# main_control.net
KiCad netlist of a schematic drawn in EasyEDA Pro
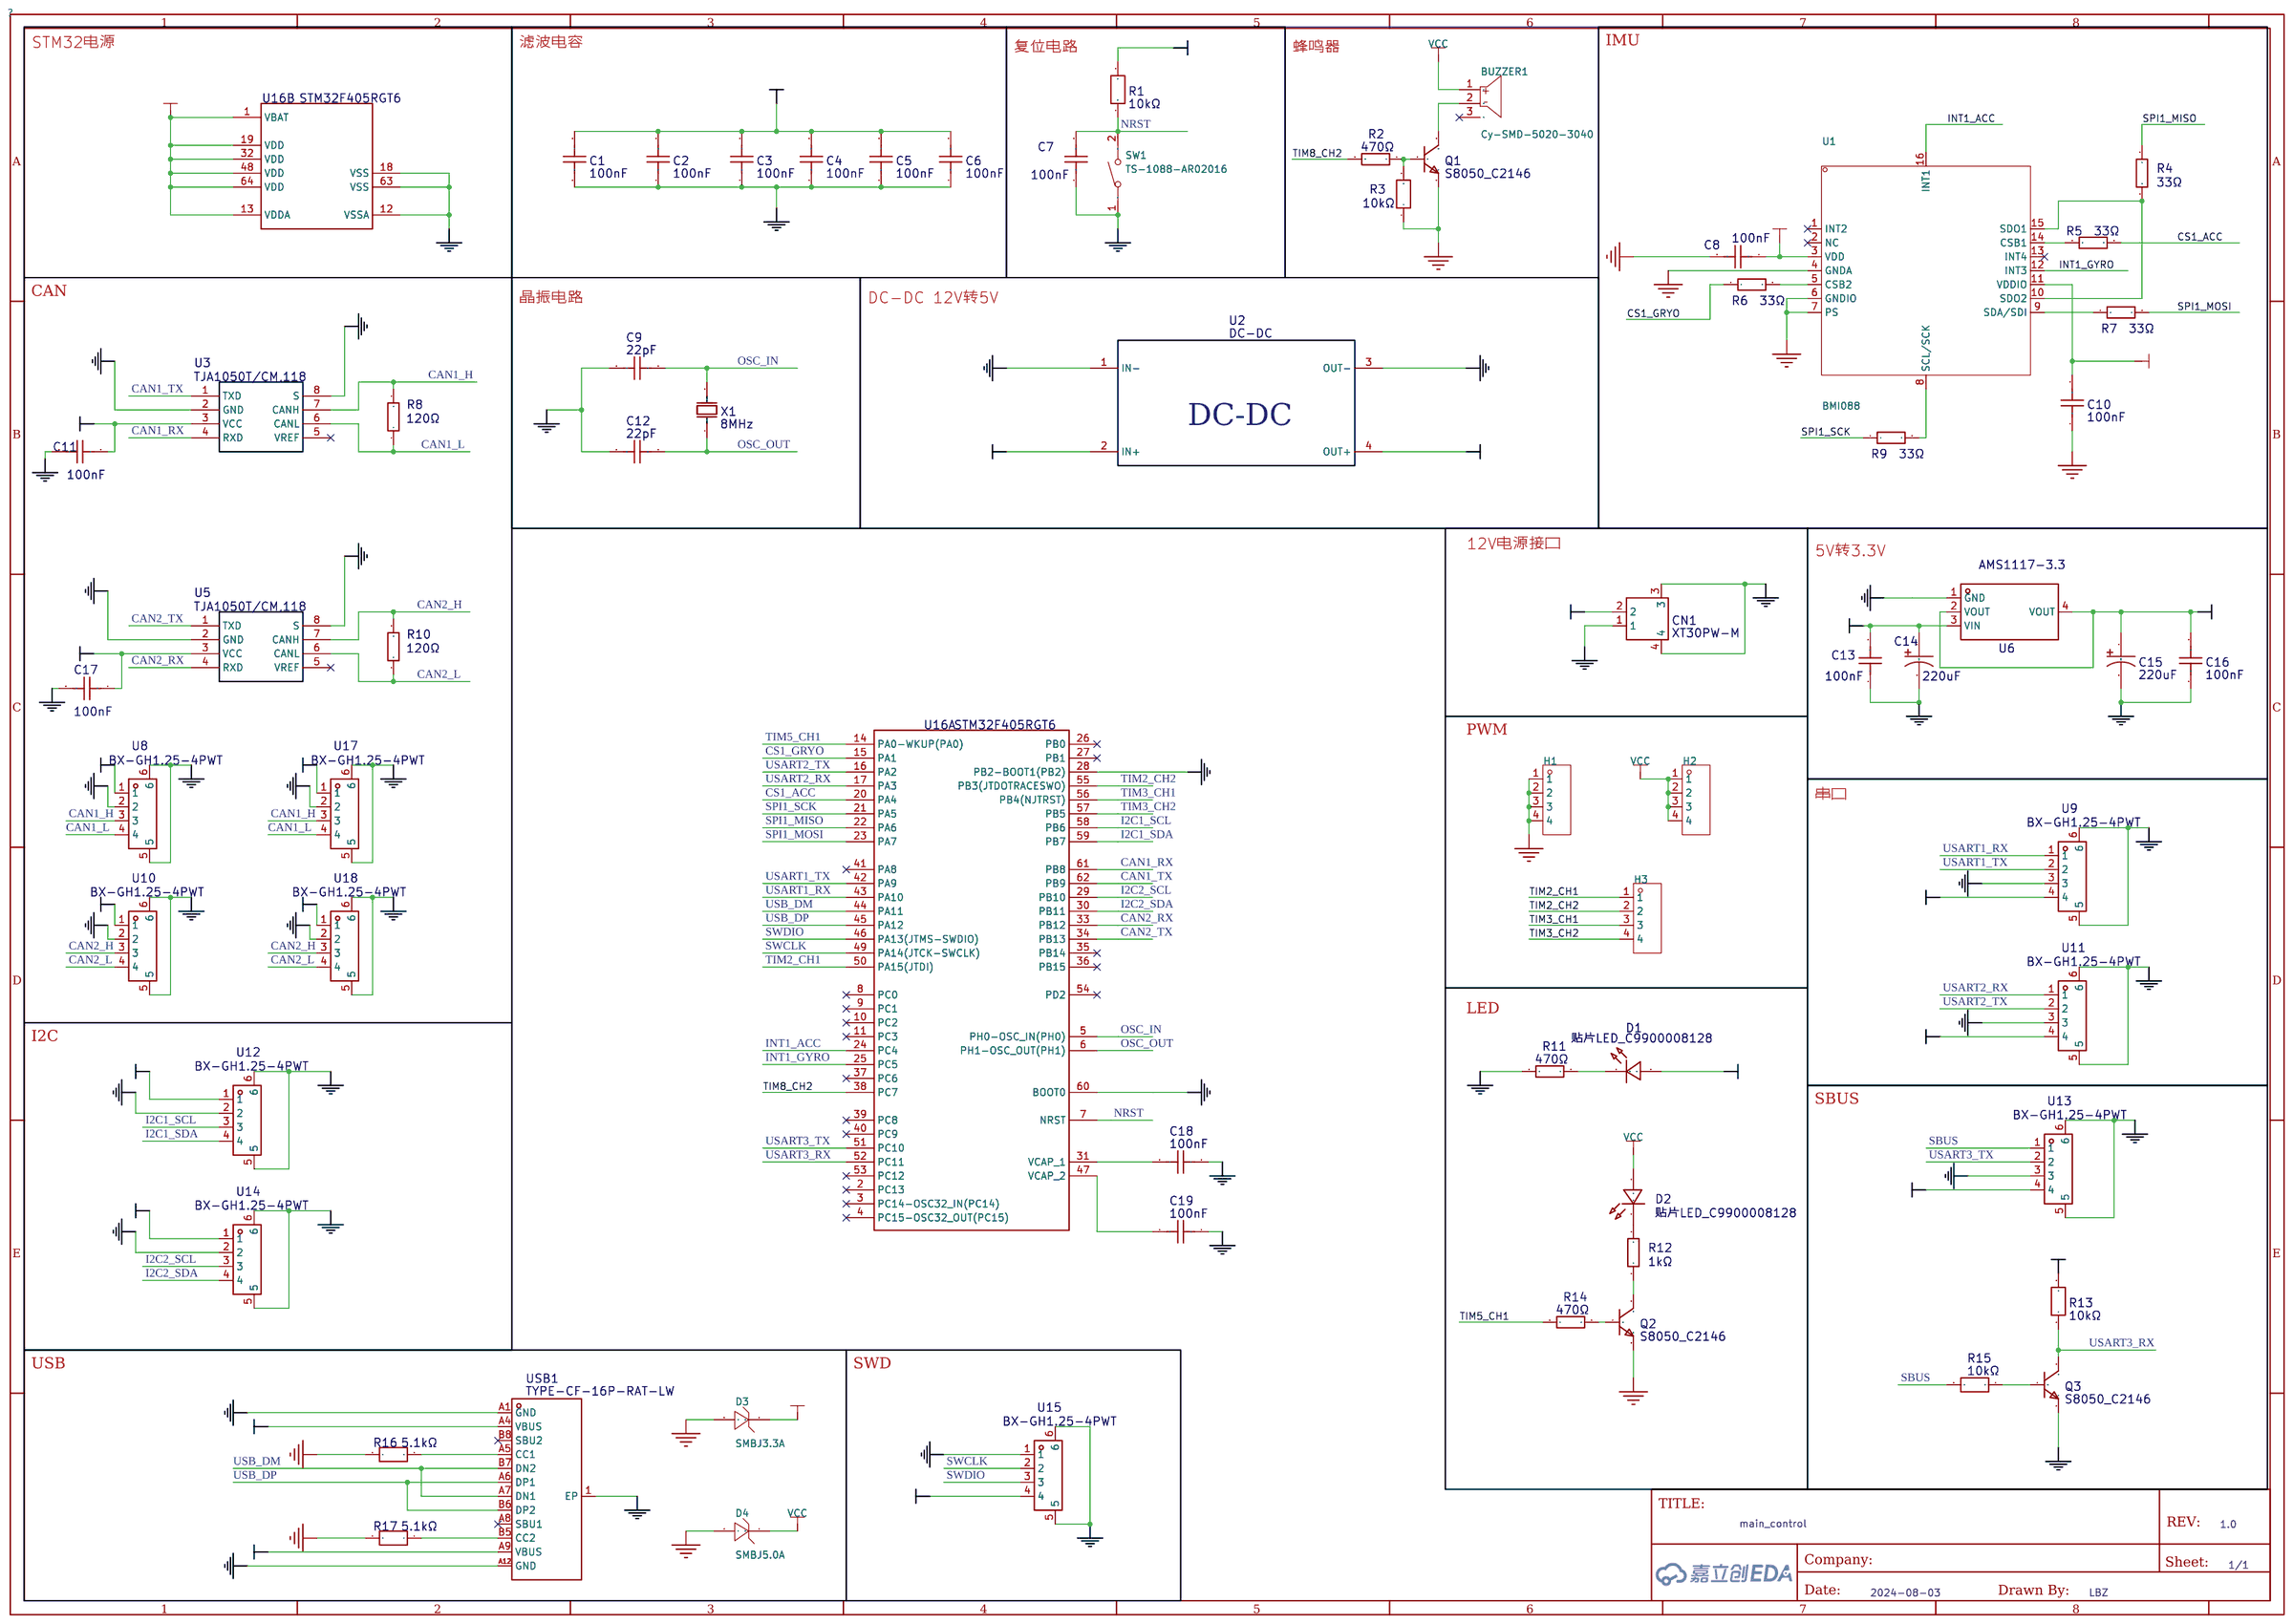
[diagram p0: schematic sheet]

(export (version "E")
  (design (tool "Eeschema 10.0.6"))
  (components
    (comp (ref "BUZZER1")
      (value "Cy-SMD-5020-3040")
      (footprint "easyedapro:BUZ-SMD_CY-SMD-5020-3040")
      (fields (field (name "Manufacturer") "CY(超音)"))
      (libsource (lib "easyedapro") (part "CY-SMD-5020-3040"))
    )
    (comp (ref "C1")
      (value "100nF")
      (footprint "easyedapro:C0603")
      (fields
        (field (name "Manufacturer Part") "0603J0250104KXR")
        (field (name "Manufacturer") "Knowles(楼氏)")
      )
      (libsource (lib "easyedapro") (part "100nF"))
    )
    (comp (ref "C2")
      (value "100nF")
      (footprint "easyedapro:C0603")
      (fields
        (field (name "Manufacturer Part") "0603J0250104KXR")
        (field (name "Manufacturer") "Knowles(楼氏)")
      )
      (libsource (lib "easyedapro") (part "100nF"))
    )
    (comp (ref "C3")
      (value "100nF")
      (footprint "easyedapro:C0603")
      (fields
        (field (name "Manufacturer Part") "0603J0250104KXR")
        (field (name "Manufacturer") "Knowles(楼氏)")
      )
      (libsource (lib "easyedapro") (part "100nF"))
    )
    (comp (ref "C4")
      (value "100nF")
      (footprint "easyedapro:C0603")
      (fields
        (field (name "Manufacturer Part") "0603J0250104KXR")
        (field (name "Manufacturer") "Knowles(楼氏)")
      )
      (libsource (lib "easyedapro") (part "100nF"))
    )
    (comp (ref "C5")
      (value "100nF")
      (footprint "easyedapro:C0603")
      (fields
        (field (name "Manufacturer Part") "0603J0250104KXR")
        (field (name "Manufacturer") "Knowles(楼氏)")
      )
      (libsource (lib "easyedapro") (part "100nF"))
    )
    (comp (ref "C6")
      (value "100nF")
      (footprint "easyedapro:C0603")
      (fields
        (field (name "Manufacturer Part") "0603J0250104KXR")
        (field (name "Manufacturer") "Knowles(楼氏)")
      )
      (libsource (lib "easyedapro") (part "100nF"))
    )
    (comp (ref "C7")
      (value "100nF")
      (footprint "easyedapro:C0603")
      (fields
        (field (name "Manufacturer Part") "0603J0250104KXR")
        (field (name "Manufacturer") "Knowles(楼氏)")
      )
      (libsource (lib "easyedapro") (part "100nF"))
    )
    (comp (ref "C8")
      (value "100nF")
      (footprint "easyedapro:C0603")
      (fields
        (field (name "Manufacturer Part") "0603J0250104KXR")
        (field (name "Manufacturer") "Knowles(楼氏)")
      )
      (libsource (lib "easyedapro") (part "100nF"))
    )
    (comp (ref "C9")
      (value "22pF")
      (footprint "easyedapro:C0603")
      (fields
        (field (name "Manufacturer Part") "0603J0250104KXR")
        (field (name "Manufacturer") "Knowles(楼氏)")
      )
      (libsource (lib "easyedapro") (part "22pF"))
    )
    (comp (ref "C10")
      (value "100nF")
      (footprint "easyedapro:C0603")
      (fields
        (field (name "Manufacturer Part") "0603J0250104KXR")
        (field (name "Manufacturer") "Knowles(楼氏)")
      )
      (libsource (lib "easyedapro") (part "100nF"))
    )
    (comp (ref "C11")
      (value "100nF")
      (footprint "easyedapro:C0603")
      (fields
        (field (name "Manufacturer Part") "0603J0250104KXR")
        (field (name "Manufacturer") "Knowles(楼氏)")
      )
      (libsource (lib "easyedapro") (part "100nF"))
    )
    (comp (ref "C12")
      (value "22pF")
      (footprint "easyedapro:C0603")
      (fields
        (field (name "Manufacturer Part") "0603J0250104KXR")
        (field (name "Manufacturer") "Knowles(楼氏)")
      )
      (libsource (lib "easyedapro") (part "22pF"))
    )
    (comp (ref "C13")
      (value "100nF")
      (footprint "easyedapro:C0603")
      (fields
        (field (name "Manufacturer Part") "0603J0250104KXR")
        (field (name "Manufacturer") "Knowles(楼氏)")
      )
      (libsource (lib "easyedapro") (part "100nF"))
    )
    (comp (ref "C14")
      (value "220uF")
      (footprint "easyedapro:CAP-SMD_BD6.3-L6.6-W6.6-FD")
      (fields
        (field (name "Manufacturer Part") "MVK 16V220M 6.3*8 6.3TP")
        (field (name "Manufacturer") "SAMYOUNG(韩国三莹)")
      )
      (libsource (lib "easyedapro") (part "220uF"))
    )
    (comp (ref "C15")
      (value "220uF")
      (footprint "easyedapro:CAP-SMD_BD6.3-L6.6-W6.6-FD")
      (fields
        (field (name "Manufacturer Part") "MVK 16V220M 6.3*8 6.3TP")
        (field (name "Manufacturer") "SAMYOUNG(韩国三莹)")
      )
      (libsource (lib "easyedapro") (part "220uF"))
    )
    (comp (ref "C16")
      (value "100nF")
      (footprint "easyedapro:C0603")
      (fields
        (field (name "Manufacturer Part") "0603J0250104KXR")
        (field (name "Manufacturer") "Knowles(楼氏)")
      )
      (libsource (lib "easyedapro") (part "100nF"))
    )
    (comp (ref "C17")
      (value "100nF")
      (footprint "easyedapro:C0603")
      (fields
        (field (name "Manufacturer Part") "0603J0250104KXR")
        (field (name "Manufacturer") "Knowles(楼氏)")
      )
      (libsource (lib "easyedapro") (part "100nF"))
    )
    (comp (ref "C18")
      (value "100nF")
      (footprint "easyedapro:C0603")
      (fields
        (field (name "Manufacturer Part") "0603J0250104KXR")
        (field (name "Manufacturer") "Knowles(楼氏)")
      )
      (libsource (lib "easyedapro") (part "100nF"))
    )
    (comp (ref "C19")
      (value "100nF")
      (footprint "easyedapro:C0603")
      (fields
        (field (name "Manufacturer Part") "0603J0250104KXR")
        (field (name "Manufacturer") "Knowles(楼氏)")
      )
      (libsource (lib "easyedapro") (part "100nF"))
    )
    (comp (ref "CN1")
      (value "XT30PW-M")
      (footprint "easyedapro:CONN-TH_XT30PW-M")
      (fields (field (name "Manufacturer") "AMASS(艾迈斯)"))
      (libsource (lib "easyedapro") (part "XT30PW-M"))
    )
    (comp (ref "D1")
      (value "贴片LED_C9900008128")
      (footprint "easyedapro:LED0603-RD")
      (fields (field (name "Manufacturer Part") "贴片LED"))
      (libsource (lib "easyedapro") (part "贴片LED_C9900008128"))
    )
    (comp (ref "D2")
      (value "贴片LED_C9900008128")
      (footprint "easyedapro:LED0603-RD")
      (fields (field (name "Manufacturer Part") "贴片LED"))
      (libsource (lib "easyedapro") (part "贴片LED_C9900008128"))
    )
    (comp (ref "D3")
      (value "SMBJ3.3A")
      (footprint "easyedapro:SMB_L4.6-W3.6-LS5.3-RD")
      (description "反向截止电压(Vrwm):3.3V;最大钳位电压:7.3V;峰值脉冲功率(Ppp)@10/1000us:600W;击穿电压:4.1V;")
      (fields (field (name "Manufacturer") "JKSEMI(金开盛)"))
      (libsource (lib "easyedapro") (part "SMBJ3.3A_C362089"))
    )
    (comp (ref "D4")
      (value "SMBJ5.0A")
      (footprint "easyedapro:SMB_L4.6-W3.6-LS5.3-RD")
      (description "反向截止电压(Vrwm):5V;最大钳位电压:9.2V;峰值脉冲电流(Ipp)@10/1000us:65.2A;击穿电压:6.4V;")
      (fields (field (name "Manufacturer") "MDD"))
      (libsource (lib "easyedapro") (part "SMBJ5.0A-C113974"))
    )
    (comp (ref "H1")
      (value "KH-2.54PH180-1X4P-L11.5")
      (footprint "easyedapro:HDR-TH_4P-P2.54-V-M")
      (fields (field (name "Manufacturer") "kinghelm(金航标)"))
      (libsource (lib "easyedapro") (part "KH-2.54PH180-1X4P-L11.5"))
    )
    (comp (ref "H2")
      (value "KH-2.54PH180-1X4P-L11.5")
      (footprint "easyedapro:HDR-TH_4P-P2.54-V-M")
      (fields (field (name "Manufacturer") "kinghelm(金航标)"))
      (libsource (lib "easyedapro") (part "KH-2.54PH180-1X4P-L11.5"))
    )
    (comp (ref "H3")
      (value "KH-2.54PH180-1X4P-L11.5")
      (footprint "easyedapro:HDR-TH_4P-P2.54-V-M")
      (fields (field (name "Manufacturer") "kinghelm(金航标)"))
      (libsource (lib "easyedapro") (part "KH-2.54PH180-1X4P-L11.5"))
    )
    (comp (ref "Q1")
      (value "S8050_C2146")
      (footprint "easyedapro:SOT-23-3_L3.0-W1.7-P0.95-LS2.9-BR")
      (fields (field (name "Manufacturer Part") "S8050 J3Y") (field (name "Manufacturer") "CJ(江苏长电/长晶)"))
      (libsource (lib "easyedapro") (part "S8050_C2146"))
    )
    (comp (ref "Q2")
      (value "S8050_C2146")
      (footprint "easyedapro:SOT-23-3_L3.0-W1.7-P0.95-LS2.9-BR")
      (fields (field (name "Manufacturer Part") "S8050 J3Y") (field (name "Manufacturer") "CJ(江苏长电/长晶)"))
      (libsource (lib "easyedapro") (part "S8050_C2146"))
    )
    (comp (ref "Q3")
      (value "S8050_C2146")
      (footprint "easyedapro:SOT-23-3_L3.0-W1.7-P0.95-LS2.9-BR")
      (fields (field (name "Manufacturer Part") "S8050 J3Y") (field (name "Manufacturer") "CJ(江苏长电/长晶)"))
      (libsource (lib "easyedapro") (part "S8050_C2146"))
    )
    (comp (ref "R1")
      (value "10kΩ")
      (footprint "easyedapro:R0603")
      (fields
        (field (name "Manufacturer Part") "MCT0603MG1002BP500")
        (field (name "Manufacturer") "VISHAY(威世)")
      )
      (libsource (lib "easyedapro") (part "10kΩ"))
    )
    (comp (ref "R2")
      (value "470Ω")
      (footprint "easyedapro:R0805")
      (fields (field (name "Manufacturer Part") "RC0805FR-07120RL") (field (name "Manufacturer") "YAGEO(国巨)"))
      (libsource (lib "easyedapro") (part "1kΩ"))
    )
    (comp (ref "R3")
      (value "10kΩ")
      (footprint "easyedapro:R0603")
      (fields
        (field (name "Manufacturer Part") "MCT0603MG1002BP500")
        (field (name "Manufacturer") "VISHAY(威世)")
      )
      (libsource (lib "easyedapro") (part "10kΩ"))
    )
    (comp (ref "R4")
      (value "33Ω")
      (footprint "easyedapro:R0805")
      (fields (field (name "Manufacturer Part") "RC0805FR-07120RL") (field (name "Manufacturer") "YAGEO(国巨)"))
      (libsource (lib "easyedapro") (part "1kΩ"))
    )
    (comp (ref "R5")
      (value "33Ω")
      (footprint "easyedapro:R0805")
      (fields (field (name "Manufacturer Part") "RC0805FR-07120RL") (field (name "Manufacturer") "YAGEO(国巨)"))
      (libsource (lib "easyedapro") (part "1kΩ"))
    )
    (comp (ref "R6")
      (value "33Ω")
      (footprint "easyedapro:R0805")
      (fields (field (name "Manufacturer Part") "RC0805FR-07120RL") (field (name "Manufacturer") "YAGEO(国巨)"))
      (libsource (lib "easyedapro") (part "1kΩ"))
    )
    (comp (ref "R7")
      (value "33Ω")
      (footprint "easyedapro:R0805")
      (fields (field (name "Manufacturer Part") "RC0805FR-07120RL") (field (name "Manufacturer") "YAGEO(国巨)"))
      (libsource (lib "easyedapro") (part "1kΩ"))
    )
    (comp (ref "R8")
      (value "120Ω")
      (footprint "easyedapro:R0805")
      (fields (field (name "Manufacturer Part") "RC0805FR-07120RL") (field (name "Manufacturer") "YAGEO(国巨)"))
      (libsource (lib "easyedapro") (part "120Ω"))
    )
    (comp (ref "R9")
      (value "33Ω")
      (footprint "easyedapro:R0805")
      (fields (field (name "Manufacturer Part") "RC0805FR-07120RL") (field (name "Manufacturer") "YAGEO(国巨)"))
      (libsource (lib "easyedapro") (part "1kΩ"))
    )
    (comp (ref "R10")
      (value "120Ω")
      (footprint "easyedapro:R0805")
      (fields (field (name "Manufacturer Part") "RC0805FR-07120RL") (field (name "Manufacturer") "YAGEO(国巨)"))
      (libsource (lib "easyedapro") (part "120Ω"))
    )
    (comp (ref "R11")
      (value "470Ω")
      (footprint "easyedapro:R0805")
      (fields (field (name "Manufacturer Part") "RC0805FR-07120RL") (field (name "Manufacturer") "YAGEO(国巨)"))
      (libsource (lib "easyedapro") (part "1kΩ"))
    )
    (comp (ref "R12")
      (value "1kΩ")
      (footprint "easyedapro:R0805")
      (fields (field (name "Manufacturer Part") "RC0805FR-07120RL") (field (name "Manufacturer") "YAGEO(国巨)"))
      (libsource (lib "easyedapro") (part "1kΩ"))
    )
    (comp (ref "R13")
      (value "10kΩ")
      (footprint "easyedapro:R0603")
      (fields
        (field (name "Manufacturer Part") "MCT0603MG1002BP500")
        (field (name "Manufacturer") "VISHAY(威世)")
      )
      (libsource (lib "easyedapro") (part "10kΩ"))
    )
    (comp (ref "R14")
      (value "470Ω")
      (footprint "easyedapro:R0805")
      (fields (field (name "Manufacturer Part") "RC0805FR-07120RL") (field (name "Manufacturer") "YAGEO(国巨)"))
      (libsource (lib "easyedapro") (part "1kΩ"))
    )
    (comp (ref "R15")
      (value "10kΩ")
      (footprint "easyedapro:R0603")
      (fields
        (field (name "Manufacturer Part") "MCT0603MG1002BP500")
        (field (name "Manufacturer") "VISHAY(威世)")
      )
      (libsource (lib "easyedapro") (part "10kΩ"))
    )
    (comp (ref "R16")
      (value "5.1kΩ")
      (footprint "easyedapro:R0603")
      (fields
        (field (name "Manufacturer Part") "MCT0603MG1002BP500")
        (field (name "Manufacturer") "VISHAY(威世)")
      )
      (libsource (lib "easyedapro") (part "10kΩ"))
    )
    (comp (ref "R17")
      (value "5.1kΩ")
      (footprint "easyedapro:R0603")
      (fields
        (field (name "Manufacturer Part") "MCT0603MG1002BP500")
        (field (name "Manufacturer") "VISHAY(威世)")
      )
      (libsource (lib "easyedapro") (part "10kΩ"))
    )
    (comp (ref "SW1")
      (value "TS-1088-AR02016")
      (footprint "easyedapro:SW-SMD_L3.9-W3.0-P4.45")
      (fields (field (name "Manufacturer") "XUNPU(讯普)"))
      (libsource (lib "easyedapro") (part "TS-1088-AR02016"))
    )
    (comp (ref "U1")
      (value "BMI088")
      (footprint "easyedapro:LGA-16_L4.5-W3.0-P0.50-BL")
      (description "传感器类型:加速度计陀螺仪;")
      (fields (field (name "Manufacturer") "Bosch(博世)"))
      (libsource (lib "easyedapro") (part "BMI088"))
    )
    (comp (ref "U2")
      (value "DC-DC")
      (footprint "easyedapro:DC-DC")
      (libsource (lib "easyedapro") (part "DC-DC"))
    )
    (comp (ref "U3")
      (value "TJA1050T/CM,118")
      (footprint "easyedapro:SOIC-8_L5.0-W4.0-P1.27-LS6.0-BL")
      (fields (field (name "Manufacturer") "NXP(恩智浦)"))
      (libsource (lib "easyedapro") (part "TJA1050T/CM,118"))
    )
    (comp (ref "U5")
      (value "TJA1050T/CM,118")
      (footprint "easyedapro:SOIC-8_L5.0-W4.0-P1.27-LS6.0-BL")
      (fields (field (name "Manufacturer") "NXP(恩智浦)"))
      (libsource (lib "easyedapro") (part "TJA1050T/CM,118"))
    )
    (comp (ref "U6")
      (value "AMS1117-3.3")
      (footprint "easyedapro:SOT-223-3_L6.5-W3.4-P2.30-LS7.0-BR")
      (fields (field (name "Manufacturer") "AMS"))
      (libsource (lib "easyedapro") (part "AMS1117-3.3"))
    )
    (comp (ref "U8")
      (value "BX-GH1.25-4PWT")
      (footprint "easyedapro:CONN-SMD_4P-P1.25_BX-GH1.25-4PWT")
      (fields (field (name "Manufacturer") "Bossie(博锡)"))
      (libsource (lib "easyedapro") (part "BX-GH1.25-4PWT"))
    )
    (comp (ref "U9")
      (value "BX-GH1.25-4PWT")
      (footprint "easyedapro:CONN-SMD_4P-P1.25_BX-GH1.25-4PWT")
      (fields (field (name "Manufacturer") "Bossie(博锡)"))
      (libsource (lib "easyedapro") (part "BX-GH1.25-4PWT"))
    )
    (comp (ref "U10")
      (value "BX-GH1.25-4PWT")
      (footprint "easyedapro:CONN-SMD_4P-P1.25_BX-GH1.25-4PWT")
      (fields (field (name "Manufacturer") "Bossie(博锡)"))
      (libsource (lib "easyedapro") (part "BX-GH1.25-4PWT"))
    )
    (comp (ref "U11")
      (value "BX-GH1.25-4PWT")
      (footprint "easyedapro:CONN-SMD_4P-P1.25_BX-GH1.25-4PWT")
      (fields (field (name "Manufacturer") "Bossie(博锡)"))
      (libsource (lib "easyedapro") (part "BX-GH1.25-4PWT"))
    )
    (comp (ref "U12")
      (value "BX-GH1.25-4PWT")
      (footprint "easyedapro:CONN-SMD_4P-P1.25_BX-GH1.25-4PWT")
      (fields (field (name "Manufacturer") "Bossie(博锡)"))
      (libsource (lib "easyedapro") (part "BX-GH1.25-4PWT"))
    )
    (comp (ref "U13")
      (value "BX-GH1.25-4PWT")
      (footprint "easyedapro:CONN-SMD_4P-P1.25_BX-GH1.25-4PWT")
      (fields (field (name "Manufacturer") "Bossie(博锡)"))
      (libsource (lib "easyedapro") (part "BX-GH1.25-4PWT"))
    )
    (comp (ref "U14")
      (value "BX-GH1.25-4PWT")
      (footprint "easyedapro:CONN-SMD_4P-P1.25_BX-GH1.25-4PWT")
      (fields (field (name "Manufacturer") "Bossie(博锡)"))
      (libsource (lib "easyedapro") (part "BX-GH1.25-4PWT"))
    )
    (comp (ref "U15")
      (value "BX-GH1.25-4PWT")
      (footprint "easyedapro:CONN-SMD_4P-P1.25_BX-GH1.25-4PWT")
      (fields (field (name "Manufacturer") "Bossie(博锡)"))
      (libsource (lib "easyedapro") (part "BX-GH1.25-4PWT"))
    )
    (comp (ref "U16")
      (value "STM32F405RGT6")
      (footprint "easyedapro:LQFP-64_L10.0-W10.0-P0.50-LS12.0-BL")
      (fields (field (name "Manufacturer") "ST(意法半导体)"))
      (libsource (lib "easyedapro") (part "STM32F405RGT6"))
    )
    (comp (ref "U17")
      (value "BX-GH1.25-4PWT")
      (footprint "easyedapro:CONN-SMD_4P-P1.25_BX-GH1.25-4PWT")
      (fields (field (name "Manufacturer") "Bossie(博锡)"))
      (libsource (lib "easyedapro") (part "BX-GH1.25-4PWT"))
    )
    (comp (ref "U18")
      (value "BX-GH1.25-4PWT")
      (footprint "easyedapro:CONN-SMD_4P-P1.25_BX-GH1.25-4PWT")
      (fields (field (name "Manufacturer") "Bossie(博锡)"))
      (libsource (lib "easyedapro") (part "BX-GH1.25-4PWT"))
    )
    (comp (ref "USB1")
      (value "TYPE-CF-16P-RAT-LW")
      (footprint "easyedapro:TYPE-C-SMD_TYPE-CF-16P-RAT-LW")
      (libsource (lib "easyedapro") (part "TYPE-CF-16P-RAT-LW"))
    )
    (comp (ref "X1")
      (value "8MHz")
      (footprint "easyedapro:HC-49US_L11.5-W4.5-P4.88")
      (fields
        (field (name "Manufacturer Part") "E49A20E00000EE10C0")
        (field (name "Manufacturer") "HOSONIC(鸿星)")
      )
      (libsource (lib "easyedapro") (part "8MHz"))
    )
  )
  (nets
    (net (code "1") (name "/CAN1_H") (class "Default")
      (node (ref "R8") (pin "2") (pinfunction "2_2") (pintype "input"))
      (node (ref "U17") (pin "3") (pinfunction "3_3") (pintype "unspecified"))
      (node (ref "U3") (pin "7") (pinfunction "CANH_7") (pintype "unspecified"))
      (node (ref "U8") (pin "3") (pinfunction "3_3") (pintype "unspecified"))
    )
    (net (code "2") (name "/CAN1_L") (class "Default")
      (node (ref "R8") (pin "1") (pinfunction "1_1") (pintype "input"))
      (node (ref "U17") (pin "4") (pinfunction "4_4") (pintype "unspecified"))
      (node (ref "U3") (pin "6") (pinfunction "CANL_6") (pintype "unspecified"))
      (node (ref "U8") (pin "4") (pinfunction "4_4") (pintype "unspecified"))
    )
    (net (code "3") (name "/CAN1_RX") (class "Default")
      (node (ref "U16") (pin "61") (pinfunction "PB8_61") (pintype "bidirectional"))
      (node (ref "U3") (pin "4") (pinfunction "RXD_4") (pintype "unspecified"))
    )
    (net (code "4") (name "/CAN1_TX") (class "Default")
      (node (ref "U16") (pin "62") (pinfunction "PB9_62") (pintype "bidirectional"))
      (node (ref "U3") (pin "1") (pinfunction "TXD_1") (pintype "unspecified"))
    )
    (net (code "5") (name "/CAN2_H") (class "Default")
      (node (ref "R10") (pin "2") (pinfunction "2_2") (pintype "input"))
      (node (ref "U10") (pin "3") (pinfunction "3_3") (pintype "unspecified"))
      (node (ref "U18") (pin "3") (pinfunction "3_3") (pintype "unspecified"))
      (node (ref "U5") (pin "7") (pinfunction "CANH_7") (pintype "unspecified"))
    )
    (net (code "6") (name "/CAN2_L") (class "Default")
      (node (ref "R10") (pin "1") (pinfunction "1_1") (pintype "input"))
      (node (ref "U10") (pin "4") (pinfunction "4_4") (pintype "unspecified"))
      (node (ref "U18") (pin "4") (pinfunction "4_4") (pintype "unspecified"))
      (node (ref "U5") (pin "6") (pinfunction "CANL_6") (pintype "unspecified"))
    )
    (net (code "7") (name "/CAN2_RX") (class "Default")
      (node (ref "U16") (pin "33") (pinfunction "PB12_33") (pintype "bidirectional"))
      (node (ref "U5") (pin "4") (pinfunction "RXD_4") (pintype "unspecified"))
    )
    (net (code "8") (name "/CAN2_TX") (class "Default")
      (node (ref "U16") (pin "34") (pinfunction "PB13_34") (pintype "bidirectional"))
      (node (ref "U5") (pin "1") (pinfunction "TXD_1") (pintype "unspecified"))
    )
    (net (code "9") (name "/CS1_ACC") (class "Default")
      (node (ref "R5") (pin "2") (pinfunction "2_2") (pintype "input"))
      (node (ref "U16") (pin "20") (pinfunction "PA4_20") (pintype "bidirectional"))
    )
    (net (code "10") (name "/CS1_GRYO") (class "Default")
      (node (ref "R6") (pin "1") (pinfunction "1_1") (pintype "input"))
      (node (ref "U16") (pin "15") (pinfunction "PA1_15") (pintype "bidirectional"))
    )
    (net (code "11") (name "/I2C1_SCL") (class "Default")
      (node (ref "U12") (pin "3") (pinfunction "3_3") (pintype "unspecified"))
      (node (ref "U16") (pin "58") (pinfunction "PB6_58") (pintype "bidirectional"))
    )
    (net (code "12") (name "/I2C1_SDA") (class "Default")
      (node (ref "U12") (pin "4") (pinfunction "4_4") (pintype "unspecified"))
      (node (ref "U16") (pin "59") (pinfunction "PB7_59") (pintype "bidirectional"))
    )
    (net (code "13") (name "/I2C2_SCL") (class "Default")
      (node (ref "U14") (pin "3") (pinfunction "3_3") (pintype "unspecified"))
      (node (ref "U16") (pin "29") (pinfunction "PB10_29") (pintype "bidirectional"))
    )
    (net (code "14") (name "/I2C2_SDA") (class "Default")
      (node (ref "U14") (pin "4") (pinfunction "4_4") (pintype "unspecified"))
      (node (ref "U16") (pin "30") (pinfunction "PB11_30") (pintype "bidirectional"))
    )
    (net (code "15") (name "/INT1_ACC") (class "Default")
      (node (ref "U1") (pin "16") (pinfunction "INT1_16") (pintype "input"))
      (node (ref "U16") (pin "24") (pinfunction "PC4_24") (pintype "bidirectional"))
    )
    (net (code "16") (name "/INT1_GYRO") (class "Default")
      (node (ref "U1") (pin "12") (pinfunction "INT3_12") (pintype "input"))
      (node (ref "U16") (pin "25") (pinfunction "PC5_25") (pintype "bidirectional"))
    )
    (net (code "17") (name "/NRST") (class "Default")
      (node (ref "C7") (pin "2") (pinfunction "2_2") (pintype "unspecified"))
      (node (ref "R1") (pin "1") (pinfunction "1_1") (pintype "unspecified"))
      (node (ref "SW1") (pin "2") (pinfunction "2_2") (pintype "unspecified"))
      (node (ref "U16") (pin "7") (pinfunction "NRST_7") (pintype "bidirectional"))
    )
    (net (code "18") (name "/OSC_IN") (class "Default")
      (node (ref "C9") (pin "1") (pinfunction "1_1") (pintype "unspecified"))
      (node (ref "U16") (pin "5") (pinfunction "PH0-OSC_IN(PH0)_5") (pintype "bidirectional"))
      (node (ref "X1") (pin "2") (pinfunction "OSC2_2") (pintype "input"))
    )
    (net (code "19") (name "/OSC_OUT") (class "Default")
      (node (ref "C12") (pin "1") (pinfunction "1_1") (pintype "unspecified"))
      (node (ref "U16") (pin "6") (pinfunction "PH1-OSC_OUT(PH1)_6") (pintype "bidirectional"))
      (node (ref "X1") (pin "1") (pinfunction "OSC1_1") (pintype "input"))
    )
    (net (code "20") (name "/SBUS") (class "Default")
      (node (ref "R15") (pin "2") (pinfunction "2_2") (pintype "unspecified"))
      (node (ref "U13") (pin "1") (pinfunction "1_1") (pintype "unspecified"))
    )
    (net (code "21") (name "/SPI1_MISO") (class "Default")
      (node (ref "R4") (pin "1") (pinfunction "1_1") (pintype "input"))
      (node (ref "U16") (pin "22") (pinfunction "PA6_22") (pintype "bidirectional"))
    )
    (net (code "22") (name "/SPI1_MOSI") (class "Default")
      (node (ref "R7") (pin "2") (pinfunction "2_2") (pintype "input"))
      (node (ref "U16") (pin "23") (pinfunction "PA7_23") (pintype "bidirectional"))
    )
    (net (code "23") (name "/SPI1_SCK") (class "Default")
      (node (ref "R9") (pin "1") (pinfunction "1_1") (pintype "input"))
      (node (ref "U16") (pin "21") (pinfunction "PA5_21") (pintype "bidirectional"))
    )
    (net (code "24") (name "/SWCLK") (class "Default")
      (node (ref "U15") (pin "2") (pinfunction "2_2") (pintype "unspecified"))
      (node (ref "U16") (pin "49") (pinfunction "PA14(JTCK-SWCLK)_49") (pintype "bidirectional"))
    )
    (net (code "25") (name "/SWDIO") (class "Default")
      (node (ref "U15") (pin "3") (pinfunction "3_3") (pintype "unspecified"))
      (node (ref "U16") (pin "46") (pinfunction "PA13(JTMS-SWDIO)_46") (pintype "bidirectional"))
    )
    (net (code "26") (name "/TIM2_CH1") (class "Default")
      (node (ref "H3") (pin "1") (pinfunction "1_1") (pintype "unspecified"))
      (node (ref "U16") (pin "50") (pinfunction "PA15(JTDI)_50") (pintype "bidirectional"))
    )
    (net (code "27") (name "/TIM2_CH2") (class "Default")
      (node (ref "H3") (pin "2") (pinfunction "2_2") (pintype "unspecified"))
      (node (ref "U16") (pin "55") (pinfunction "PB3(JTDOTRACESWO)_55") (pintype "bidirectional"))
    )
    (net (code "28") (name "/TIM3_CH1") (class "Default")
      (node (ref "H3") (pin "3") (pinfunction "3_3") (pintype "unspecified"))
      (node (ref "U16") (pin "56") (pinfunction "PB4(NJTRST)_56") (pintype "bidirectional"))
    )
    (net (code "29") (name "/TIM3_CH2") (class "Default")
      (node (ref "H3") (pin "4") (pinfunction "4_4") (pintype "unspecified"))
      (node (ref "U16") (pin "57") (pinfunction "PB5_57") (pintype "bidirectional"))
    )
    (net (code "30") (name "/TIM5_CH1") (class "Default")
      (node (ref "R14") (pin "2") (pinfunction "2_2") (pintype "input"))
      (node (ref "U16") (pin "14") (pinfunction "PA0-WKUP(PA0)_14") (pintype "bidirectional"))
    )
    (net (code "31") (name "/TIM8_CH2") (class "Default")
      (node (ref "R2") (pin "2") (pinfunction "2_2") (pintype "input"))
      (node (ref "U16") (pin "38") (pinfunction "PC7_38") (pintype "bidirectional"))
    )
    (net (code "32") (name "/USART1_RX") (class "Default")
      (node (ref "U16") (pin "43") (pinfunction "PA10_43") (pintype "bidirectional"))
      (node (ref "U9") (pin "1") (pinfunction "1_1") (pintype "unspecified"))
    )
    (net (code "33") (name "/USART1_TX") (class "Default")
      (node (ref "U16") (pin "42") (pinfunction "PA9_42") (pintype "bidirectional"))
      (node (ref "U9") (pin "2") (pinfunction "2_2") (pintype "unspecified"))
    )
    (net (code "34") (name "/USART2_RX") (class "Default")
      (node (ref "U11") (pin "1") (pinfunction "1_1") (pintype "unspecified"))
      (node (ref "U16") (pin "17") (pinfunction "PA3_17") (pintype "bidirectional"))
    )
    (net (code "35") (name "/USART2_TX") (class "Default")
      (node (ref "U11") (pin "2") (pinfunction "2_2") (pintype "unspecified"))
      (node (ref "U16") (pin "16") (pinfunction "PA2_16") (pintype "bidirectional"))
    )
    (net (code "36") (name "/USART3_RX") (class "Default")
      (node (ref "Q3") (pin "3") (pinfunction "C_3") (pintype "unspecified"))
      (node (ref "R13") (pin "1") (pinfunction "1_1") (pintype "unspecified"))
      (node (ref "U16") (pin "52") (pinfunction "PC11_52") (pintype "bidirectional"))
    )
    (net (code "37") (name "/USART3_TX") (class "Default")
      (node (ref "U13") (pin "2") (pinfunction "2_2") (pintype "unspecified"))
      (node (ref "U16") (pin "51") (pinfunction "PC10_51") (pintype "bidirectional"))
    )
    (net (code "38") (name "/USB_DM") (class "Default")
      (node (ref "U16") (pin "44") (pinfunction "PA11_44") (pintype "bidirectional"))
      (node (ref "USB1") (pin "A7") (pinfunction "DN1_A7") (pintype "unspecified"))
      (node (ref "USB1") (pin "B7") (pinfunction "DN2_B7") (pintype "unspecified"))
    )
    (net (code "39") (name "/USB_DP") (class "Default")
      (node (ref "U16") (pin "45") (pinfunction "PA12_45") (pintype "bidirectional"))
      (node (ref "USB1") (pin "A6") (pinfunction "DP1_A6") (pintype "unspecified"))
      (node (ref "USB1") (pin "B6") (pinfunction "DP2_B6") (pintype "unspecified"))
    )
    (net (code "40") (name "GND") (class "Default")
      (node (ref "C1") (pin "1") (pinfunction "1_1") (pintype "unspecified"))
      (node (ref "C10") (pin "1") (pinfunction "1_1") (pintype "unspecified"))
      (node (ref "C11") (pin "2") (pinfunction "2_2") (pintype "unspecified"))
      (node (ref "C12") (pin "2") (pinfunction "2_2") (pintype "unspecified"))
      (node (ref "C13") (pin "1") (pinfunction "1_1") (pintype "unspecified"))
      (node (ref "C14") (pin "2") (pinfunction "2_2") (pintype "unspecified"))
      (node (ref "C15") (pin "2") (pinfunction "2_2") (pintype "unspecified"))
      (node (ref "C16") (pin "1") (pinfunction "1_1") (pintype "unspecified"))
      (node (ref "C17") (pin "2") (pinfunction "2_2") (pintype "unspecified"))
      (node (ref "C18") (pin "1") (pinfunction "1_1") (pintype "unspecified"))
      (node (ref "C19") (pin "1") (pinfunction "1_1") (pintype "unspecified"))
      (node (ref "C2") (pin "1") (pinfunction "1_1") (pintype "unspecified"))
      (node (ref "C3") (pin "1") (pinfunction "1_1") (pintype "unspecified"))
      (node (ref "C4") (pin "1") (pinfunction "1_1") (pintype "unspecified"))
      (node (ref "C5") (pin "1") (pinfunction "1_1") (pintype "unspecified"))
      (node (ref "C6") (pin "1") (pinfunction "1_1") (pintype "unspecified"))
      (node (ref "C7") (pin "1") (pinfunction "1_1") (pintype "unspecified"))
      (node (ref "C8") (pin "2") (pinfunction "2_2") (pintype "unspecified"))
      (node (ref "C9") (pin "2") (pinfunction "2_2") (pintype "unspecified"))
      (node (ref "D3") (pin "2") (pinfunction "2_2") (pintype "input"))
      (node (ref "D4") (pin "2") (pinfunction "A_2") (pintype "unspecified"))
      (node (ref "H1") (pin "1") (pinfunction "1_1") (pintype "unspecified"))
      (node (ref "H1") (pin "2") (pinfunction "2_2") (pintype "unspecified"))
      (node (ref "H1") (pin "3") (pinfunction "3_3") (pintype "unspecified"))
      (node (ref "H1") (pin "4") (pinfunction "4_4") (pintype "unspecified"))
      (node (ref "Q1") (pin "2") (pinfunction "E_2") (pintype "unspecified"))
      (node (ref "Q2") (pin "2") (pinfunction "E_2") (pintype "unspecified"))
      (node (ref "Q3") (pin "2") (pinfunction "E_2") (pintype "unspecified"))
      (node (ref "R11") (pin "2") (pinfunction "2_2") (pintype "input"))
      (node (ref "R16") (pin "2") (pinfunction "2_2") (pintype "unspecified"))
      (node (ref "R17") (pin "2") (pinfunction "2_2") (pintype "unspecified"))
      (node (ref "R3") (pin "1") (pinfunction "1_1") (pintype "unspecified"))
      (node (ref "SW1") (pin "1") (pinfunction "1_1") (pintype "unspecified"))
      (node (ref "U1") (pin "4") (pinfunction "GNDA_4") (pintype "input"))
      (node (ref "U1") (pin "6") (pinfunction "GNDIO_6") (pintype "input"))
      (node (ref "U1") (pin "7") (pinfunction "PS_7") (pintype "input"))
      (node (ref "U10") (pin "2") (pinfunction "2_2") (pintype "unspecified"))
      (node (ref "U10") (pin "5") (pinfunction "5_5") (pintype "unspecified"))
      (node (ref "U10") (pin "6") (pinfunction "6_6") (pintype "unspecified"))
      (node (ref "U11") (pin "3") (pinfunction "3_3") (pintype "unspecified"))
      (node (ref "U11") (pin "5") (pinfunction "5_5") (pintype "unspecified"))
      (node (ref "U11") (pin "6") (pinfunction "6_6") (pintype "unspecified"))
      (node (ref "U12") (pin "2") (pinfunction "2_2") (pintype "unspecified"))
      (node (ref "U12") (pin "5") (pinfunction "5_5") (pintype "unspecified"))
      (node (ref "U12") (pin "6") (pinfunction "6_6") (pintype "unspecified"))
      (node (ref "U13") (pin "3") (pinfunction "3_3") (pintype "unspecified"))
      (node (ref "U13") (pin "5") (pinfunction "5_5") (pintype "unspecified"))
      (node (ref "U13") (pin "6") (pinfunction "6_6") (pintype "unspecified"))
      (node (ref "U14") (pin "2") (pinfunction "2_2") (pintype "unspecified"))
      (node (ref "U14") (pin "5") (pinfunction "5_5") (pintype "unspecified"))
      (node (ref "U14") (pin "6") (pinfunction "6_6") (pintype "unspecified"))
      (node (ref "U15") (pin "1") (pinfunction "1_1") (pintype "unspecified"))
      (node (ref "U15") (pin "5") (pinfunction "5_5") (pintype "unspecified"))
      (node (ref "U15") (pin "6") (pinfunction "6_6") (pintype "unspecified"))
      (node (ref "U16") (pin "12") (pinfunction "VSSA_12") (pintype "unspecified"))
      (node (ref "U16") (pin "18") (pinfunction "VSS_18") (pintype "unspecified"))
      (node (ref "U16") (pin "28") (pinfunction "PB2-BOOT1(PB2)_28") (pintype "bidirectional"))
      (node (ref "U16") (pin "60") (pinfunction "BOOT0_60") (pintype "unspecified"))
      (node (ref "U16") (pin "63") (pinfunction "VSS_63") (pintype "unspecified"))
      (node (ref "U17") (pin "2") (pinfunction "2_2") (pintype "unspecified"))
      (node (ref "U17") (pin "5") (pinfunction "5_5") (pintype "unspecified"))
      (node (ref "U17") (pin "6") (pinfunction "6_6") (pintype "unspecified"))
      (node (ref "U18") (pin "2") (pinfunction "2_2") (pintype "unspecified"))
      (node (ref "U18") (pin "5") (pinfunction "5_5") (pintype "unspecified"))
      (node (ref "U18") (pin "6") (pinfunction "6_6") (pintype "unspecified"))
      (node (ref "U2") (pin "3") (pinfunction "OUT-_3") (pintype "unspecified"))
      (node (ref "U3") (pin "2") (pinfunction "GND_2") (pintype "unspecified"))
      (node (ref "U3") (pin "8") (pinfunction "S_8") (pintype "unspecified"))
      (node (ref "U5") (pin "2") (pinfunction "GND_2") (pintype "unspecified"))
      (node (ref "U5") (pin "8") (pinfunction "S_8") (pintype "unspecified"))
      (node (ref "U6") (pin "1") (pinfunction "GND_1") (pintype "unspecified"))
      (node (ref "U8") (pin "2") (pinfunction "2_2") (pintype "unspecified"))
      (node (ref "U8") (pin "5") (pinfunction "5_5") (pintype "unspecified"))
      (node (ref "U8") (pin "6") (pinfunction "6_6") (pintype "unspecified"))
      (node (ref "U9") (pin "3") (pinfunction "3_3") (pintype "unspecified"))
      (node (ref "U9") (pin "5") (pinfunction "5_5") (pintype "unspecified"))
      (node (ref "U9") (pin "6") (pinfunction "6_6") (pintype "unspecified"))
      (node (ref "USB1") (pin "1") (pinfunction "EP_1") (pintype "unspecified"))
      (node (ref "USB1") (pin "A1") (pinfunction "GND_A1") (pintype "unspecified"))
      (node (ref "USB1") (pin "A12") (pinfunction "GND_A12") (pintype "unspecified"))
    )
    (net (code "41") (name "Net-(D1-Pad1)") (class "Default")
      (node (ref "D1") (pin "1") (pinfunction "1_1") (pintype "unspecified"))
      (node (ref "R11") (pin "1") (pinfunction "1_1") (pintype "input"))
    )
    (net (code "42") (name "Net-(D2-Pad1)") (class "Default")
      (node (ref "D2") (pin "1") (pinfunction "1_1") (pintype "unspecified"))
      (node (ref "R12") (pin "1") (pinfunction "1_1") (pintype "input"))
    )
    (net (code "43") (name "Net-(Q1-B)") (class "Default")
      (node (ref "Q1") (pin "1") (pinfunction "B_1") (pintype "unspecified"))
      (node (ref "R2") (pin "1") (pinfunction "1_1") (pintype "input"))
      (node (ref "R3") (pin "2") (pinfunction "2_2") (pintype "unspecified"))
    )
    (net (code "44") (name "Net-(Q1-C)") (class "Default")
      (node (ref "BUZZER1") (pin "2") (pinfunction "2_2") (pintype "unspecified"))
      (node (ref "Q1") (pin "3") (pinfunction "C_3") (pintype "unspecified"))
    )
    (net (code "45") (name "Net-(Q2-B)") (class "Default")
      (node (ref "Q2") (pin "1") (pinfunction "B_1") (pintype "unspecified"))
      (node (ref "R14") (pin "1") (pinfunction "1_1") (pintype "input"))
    )
    (net (code "46") (name "Net-(Q2-C)") (class "Default")
      (node (ref "Q2") (pin "3") (pinfunction "C_3") (pintype "unspecified"))
      (node (ref "R12") (pin "2") (pinfunction "2_2") (pintype "input"))
    )
    (net (code "47") (name "Net-(Q3-B)") (class "Default")
      (node (ref "Q3") (pin "1") (pinfunction "B_1") (pintype "unspecified"))
      (node (ref "R15") (pin "1") (pinfunction "1_1") (pintype "unspecified"))
    )
    (net (code "48") (name "Net-(U1-CSB1)") (class "Default")
      (node (ref "R5") (pin "1") (pinfunction "1_1") (pintype "input"))
      (node (ref "U1") (pin "14") (pinfunction "CSB1_14") (pintype "input"))
    )
    (net (code "49") (name "Net-(U1-CSB2)") (class "Default")
      (node (ref "R6") (pin "2") (pinfunction "2_2") (pintype "input"))
      (node (ref "U1") (pin "5") (pinfunction "CSB2_5") (pintype "input"))
    )
    (net (code "50") (name "Net-(U1-SCL{slash}SCK)") (class "Default")
      (node (ref "R9") (pin "2") (pinfunction "2_2") (pintype "input"))
      (node (ref "U1") (pin "8") (pinfunction "SCL/SCK_8") (pintype "input"))
    )
    (net (code "51") (name "Net-(U1-SDA{slash}SDI)") (class "Default")
      (node (ref "R7") (pin "1") (pinfunction "1_1") (pintype "input"))
      (node (ref "U1") (pin "9") (pinfunction "SDA/SDI_9") (pintype "input"))
    )
    (net (code "52") (name "Net-(U1-SDO1)") (class "Default")
      (node (ref "R4") (pin "2") (pinfunction "2_2") (pintype "input"))
      (node (ref "U1") (pin "10") (pinfunction "SDO2_10") (pintype "input"))
      (node (ref "U1") (pin "15") (pinfunction "SDO1_15") (pintype "input"))
    )
    (net (code "53") (name "Net-(U16A-VCAP_1)") (class "Default")
      (node (ref "C18") (pin "2") (pinfunction "2_2") (pintype "unspecified"))
      (node (ref "U16") (pin "31") (pinfunction "VCAP_1_31") (pintype "unspecified"))
    )
    (net (code "54") (name "Net-(U16A-VCAP_2)") (class "Default")
      (node (ref "C19") (pin "2") (pinfunction "2_2") (pintype "unspecified"))
      (node (ref "U16") (pin "47") (pinfunction "VCAP_2_47") (pintype "unspecified"))
    )
    (net (code "55") (name "Net-(USB1-CC1)") (class "Default")
      (node (ref "R16") (pin "1") (pinfunction "1_1") (pintype "unspecified"))
      (node (ref "USB1") (pin "A5") (pinfunction "CC1_A5") (pintype "unspecified"))
    )
    (net (code "56") (name "Net-(USB1-CC2)") (class "Default")
      (node (ref "R17") (pin "1") (pinfunction "1_1") (pintype "unspecified"))
      (node (ref "USB1") (pin "B5") (pinfunction "CC2_B5") (pintype "unspecified"))
    )
    (net (code "57") (name "PGND") (class "Default")
      (node (ref "CN1") (pin "1") (pinfunction "1_1") (pintype "unspecified"))
      (node (ref "CN1") (pin "3") (pinfunction "3_3") (pintype "unspecified"))
      (node (ref "CN1") (pin "4") (pinfunction "4_4") (pintype "unspecified"))
      (node (ref "U2") (pin "1") (pinfunction "IN-_1") (pintype "unspecified"))
    )
    (net (code "58") (name "VCC") (class "Default")
      (node (ref "BUZZER1") (pin "1") (pinfunction "1_1") (pintype "unspecified"))
      (node (ref "C11") (pin "1") (pinfunction "1_1") (pintype "unspecified"))
      (node (ref "C13") (pin "2") (pinfunction "2_2") (pintype "unspecified"))
      (node (ref "C14") (pin "1") (pinfunction "1_1") (pintype "unspecified"))
      (node (ref "C17") (pin "1") (pinfunction "1_1") (pintype "unspecified"))
      (node (ref "D2") (pin "2") (pinfunction "2_2") (pintype "unspecified"))
      (node (ref "D4") (pin "1") (pinfunction "C_1") (pintype "unspecified"))
      (node (ref "H2") (pin "1") (pinfunction "1_1") (pintype "unspecified"))
      (node (ref "H2") (pin "2") (pinfunction "2_2") (pintype "unspecified"))
      (node (ref "H2") (pin "3") (pinfunction "3_3") (pintype "unspecified"))
      (node (ref "H2") (pin "4") (pinfunction "4_4") (pintype "unspecified"))
      (node (ref "U10") (pin "1") (pinfunction "1_1") (pintype "unspecified"))
      (node (ref "U11") (pin "4") (pinfunction "4_4") (pintype "unspecified"))
      (node (ref "U12") (pin "1") (pinfunction "1_1") (pintype "unspecified"))
      (node (ref "U13") (pin "4") (pinfunction "4_4") (pintype "unspecified"))
      (node (ref "U14") (pin "1") (pinfunction "1_1") (pintype "unspecified"))
      (node (ref "U17") (pin "1") (pinfunction "1_1") (pintype "unspecified"))
      (node (ref "U18") (pin "1") (pinfunction "1_1") (pintype "unspecified"))
      (node (ref "U2") (pin "4") (pinfunction "OUT+_4") (pintype "unspecified"))
      (node (ref "U3") (pin "3") (pinfunction "VCC_3") (pintype "unspecified"))
      (node (ref "U5") (pin "3") (pinfunction "VCC_3") (pintype "unspecified"))
      (node (ref "U6") (pin "3") (pinfunction "VIN_3") (pintype "unspecified"))
      (node (ref "U8") (pin "1") (pinfunction "1_1") (pintype "unspecified"))
      (node (ref "U9") (pin "4") (pinfunction "4_4") (pintype "unspecified"))
      (node (ref "USB1") (pin "A4") (pinfunction "VBUS_A4") (pintype "unspecified"))
      (node (ref "USB1") (pin "A9") (pinfunction "VBUS_A9") (pintype "unspecified"))
    )
    (net (code "59") (name "VCC3.3") (class "Default")
      (node (ref "C1") (pin "2") (pinfunction "2_2") (pintype "unspecified"))
      (node (ref "C10") (pin "2") (pinfunction "2_2") (pintype "unspecified"))
      (node (ref "C15") (pin "1") (pinfunction "1_1") (pintype "unspecified"))
      (node (ref "C16") (pin "2") (pinfunction "2_2") (pintype "unspecified"))
      (node (ref "C2") (pin "2") (pinfunction "2_2") (pintype "unspecified"))
      (node (ref "C3") (pin "2") (pinfunction "2_2") (pintype "unspecified"))
      (node (ref "C4") (pin "2") (pinfunction "2_2") (pintype "unspecified"))
      (node (ref "C5") (pin "2") (pinfunction "2_2") (pintype "unspecified"))
      (node (ref "C6") (pin "2") (pinfunction "2_2") (pintype "unspecified"))
      (node (ref "C8") (pin "1") (pinfunction "1_1") (pintype "unspecified"))
      (node (ref "D1") (pin "2") (pinfunction "2_2") (pintype "unspecified"))
      (node (ref "D3") (pin "1") (pinfunction "1_1") (pintype "input"))
      (node (ref "R1") (pin "2") (pinfunction "2_2") (pintype "unspecified"))
      (node (ref "R13") (pin "2") (pinfunction "2_2") (pintype "unspecified"))
      (node (ref "U1") (pin "11") (pinfunction "VDDIO_11") (pintype "input"))
      (node (ref "U1") (pin "3") (pinfunction "VDD_3") (pintype "input"))
      (node (ref "U15") (pin "4") (pinfunction "4_4") (pintype "unspecified"))
      (node (ref "U16") (pin "1") (pinfunction "VBAT_1") (pintype "unspecified"))
      (node (ref "U16") (pin "13") (pinfunction "VDDA_13") (pintype "unspecified"))
      (node (ref "U16") (pin "19") (pinfunction "VDD_19") (pintype "unspecified"))
      (node (ref "U16") (pin "32") (pinfunction "VDD_32") (pintype "unspecified"))
      (node (ref "U16") (pin "48") (pinfunction "VDD_48") (pintype "unspecified"))
      (node (ref "U16") (pin "64") (pinfunction "VDD_64") (pintype "unspecified"))
      (node (ref "U6") (pin "2") (pinfunction "VOUT_2") (pintype "unspecified"))
      (node (ref "U6") (pin "4") (pinfunction "VOUT_4") (pintype "unspecified"))
    )
    (net (code "60") (name "VCC12V") (class "Default")
      (node (ref "CN1") (pin "2") (pinfunction "2_2") (pintype "unspecified"))
      (node (ref "U2") (pin "2") (pinfunction "IN+_2") (pintype "unspecified"))
    )
    (net (code "61") (name "unconnected-(BUZZER1-Pad3)") (class "Default")
      (node (ref "BUZZER1") (pin "3") (pinfunction "3_3") (pintype "unspecified+no_connect"))
    )
    (net (code "62") (name "unconnected-(U1-INT2-Pad1)") (class "Default")
      (node (ref "U1") (pin "1") (pinfunction "INT2_1") (pintype "input+no_connect"))
    )
    (net (code "63") (name "unconnected-(U1-INT4-Pad13)") (class "Default")
      (node (ref "U1") (pin "13") (pinfunction "INT4_13") (pintype "input+no_connect"))
    )
    (net (code "64") (name "unconnected-(U1-NC-Pad2)") (class "Default")
      (node (ref "U1") (pin "2") (pinfunction "NC_2") (pintype "input+no_connect"))
    )
    (net (code "65") (name "unconnected-(U3-VREF-Pad5)") (class "Default")
      (node (ref "U3") (pin "5") (pinfunction "VREF_5") (pintype "unspecified+no_connect"))
    )
    (net (code "66") (name "unconnected-(U5-VREF-Pad5)") (class "Default")
      (node (ref "U5") (pin "5") (pinfunction "VREF_5") (pintype "unspecified+no_connect"))
    )
    (net (code "67") (name "unconnected-(U16A-PA8-Pad41)") (class "Default")
      (node (ref "U16") (pin "41") (pinfunction "PA8_41") (pintype "bidirectional+no_connect"))
    )
    (net (code "68") (name "unconnected-(U16A-PB0-Pad26)") (class "Default")
      (node (ref "U16") (pin "26") (pinfunction "PB0_26") (pintype "bidirectional+no_connect"))
    )
    (net (code "69") (name "unconnected-(U16A-PB1-Pad27)") (class "Default")
      (node (ref "U16") (pin "27") (pinfunction "PB1_27") (pintype "bidirectional+no_connect"))
    )
    (net (code "70") (name "unconnected-(U16A-PB14-Pad35)") (class "Default")
      (node (ref "U16") (pin "35") (pinfunction "PB14_35") (pintype "bidirectional+no_connect"))
    )
    (net (code "71") (name "unconnected-(U16A-PB15-Pad36)") (class "Default")
      (node (ref "U16") (pin "36") (pinfunction "PB15_36") (pintype "bidirectional+no_connect"))
    )
    (net (code "72") (name "unconnected-(U16A-PC0-Pad8)") (class "Default")
      (node (ref "U16") (pin "8") (pinfunction "PC0_8") (pintype "bidirectional+no_connect"))
    )
    (net (code "73") (name "unconnected-(U16A-PC1-Pad9)") (class "Default")
      (node (ref "U16") (pin "9") (pinfunction "PC1_9") (pintype "bidirectional+no_connect"))
    )
    (net (code "74") (name "unconnected-(U16A-PC2-Pad10)") (class "Default")
      (node (ref "U16") (pin "10") (pinfunction "PC2_10") (pintype "bidirectional+no_connect"))
    )
    (net (code "75") (name "unconnected-(U16A-PC3-Pad11)") (class "Default")
      (node (ref "U16") (pin "11") (pinfunction "PC3_11") (pintype "bidirectional+no_connect"))
    )
    (net (code "76") (name "unconnected-(U16A-PC6-Pad37)") (class "Default")
      (node (ref "U16") (pin "37") (pinfunction "PC6_37") (pintype "bidirectional+no_connect"))
    )
    (net (code "77") (name "unconnected-(U16A-PC8-Pad39)") (class "Default")
      (node (ref "U16") (pin "39") (pinfunction "PC8_39") (pintype "bidirectional+no_connect"))
    )
    (net (code "78") (name "unconnected-(U16A-PC9-Pad40)") (class "Default")
      (node (ref "U16") (pin "40") (pinfunction "PC9_40") (pintype "bidirectional+no_connect"))
    )
    (net (code "79") (name "unconnected-(U16A-PC12-Pad53)") (class "Default")
      (node (ref "U16") (pin "53") (pinfunction "PC12_53") (pintype "bidirectional+no_connect"))
    )
    (net (code "80") (name "unconnected-(U16A-PC13-Pad2)") (class "Default")
      (node (ref "U16") (pin "2") (pinfunction "PC13_2") (pintype "bidirectional+no_connect"))
    )
    (net (code "81") (name "unconnected-(U16A-PC14-OSC32_IN(PC14)-Pad3)") (class "Default")
      (node (ref "U16") (pin "3") (pinfunction "PC14-OSC32_IN(PC14)_3") (pintype "bidirectional+no_connect"))
    )
    (net (code "82") (name "unconnected-(U16A-PC15-OSC32_OUT(PC15)-Pad4)") (class "Default")
      (node (ref "U16") (pin "4") (pinfunction "PC15-OSC32_OUT(PC15)_4") (pintype "bidirectional+no_connect"))
    )
    (net (code "83") (name "unconnected-(U16A-PD2-Pad54)") (class "Default")
      (node (ref "U16") (pin "54") (pinfunction "PD2_54") (pintype "bidirectional+no_connect"))
    )
    (net (code "84") (name "unconnected-(USB1-SBU1-PadA8)") (class "Default")
      (node (ref "USB1") (pin "A8") (pinfunction "SBU1_A8") (pintype "unspecified+no_connect"))
    )
    (net (code "85") (name "unconnected-(USB1-SBU2-PadB8)") (class "Default")
      (node (ref "USB1") (pin "B8") (pinfunction "SBU2_B8") (pintype "unspecified+no_connect"))
    )
  )
)
